# ETHERNET.net
KiCad netlist of a schematic drawn in Altium Designer
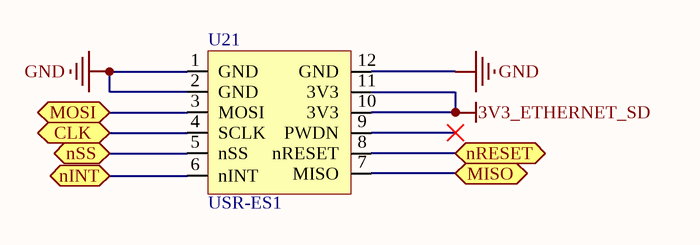
[diagram p0: ETHERNET.SchDoc]

(export (version "E")
  (design (tool "Eeschema 10.0.6"))
  (components
    (comp (ref "U21")
      (value "USR-ES1")
      (footprint "USR-ES1")
      (description "Ethernet module")
      (libsource (lib "CMN") (part "USR-ES1"))
    )
  )
  (nets
    (net (code "1") (name "/CLK") (class "Default")
      (node (ref "U21") (pin "4") (pinfunction "SCLK_4") (pintype "passive"))
    )
    (net (code "2") (name "/MISO") (class "Default")
      (node (ref "U21") (pin "7") (pinfunction "MISO_7") (pintype "passive"))
    )
    (net (code "3") (name "/MOSI") (class "Default")
      (node (ref "U21") (pin "3") (pinfunction "MOSI_3") (pintype "passive"))
    )
    (net (code "4") (name "/nINT") (class "Default")
      (node (ref "U21") (pin "6") (pinfunction "nINT_6") (pintype "passive"))
    )
    (net (code "5") (name "/nRESET") (class "Default")
      (node (ref "U21") (pin "8") (pinfunction "nRESET_8") (pintype "passive"))
    )
    (net (code "6") (name "/nSS") (class "Default")
      (node (ref "U21") (pin "5") (pinfunction "nSS_5") (pintype "passive"))
    )
    (net (code "7") (name "3V3_ETHERNET_SD") (class "Default")
      (node (ref "U21") (pin "10") (pinfunction "3V3_10") (pintype "passive"))
      (node (ref "U21") (pin "11") (pinfunction "3V3_11") (pintype "passive"))
    )
    (net (code "8") (name "GND") (class "Default")
      (node (ref "U21") (pin "1") (pinfunction "GND_1") (pintype "passive"))
      (node (ref "U21") (pin "12") (pinfunction "GND_12") (pintype "passive"))
      (node (ref "U21") (pin "2") (pinfunction "GND_2") (pintype "passive"))
    )
    (net (code "9") (name "unconnected-(U21-PWDN-Pad9)") (class "Default")
      (node (ref "U21") (pin "9") (pinfunction "PWDN_9") (pintype "passive+no_connect"))
    )
  )
)
